# Microcontroller.net
KiCad netlist of a schematic drawn in Altium Designer
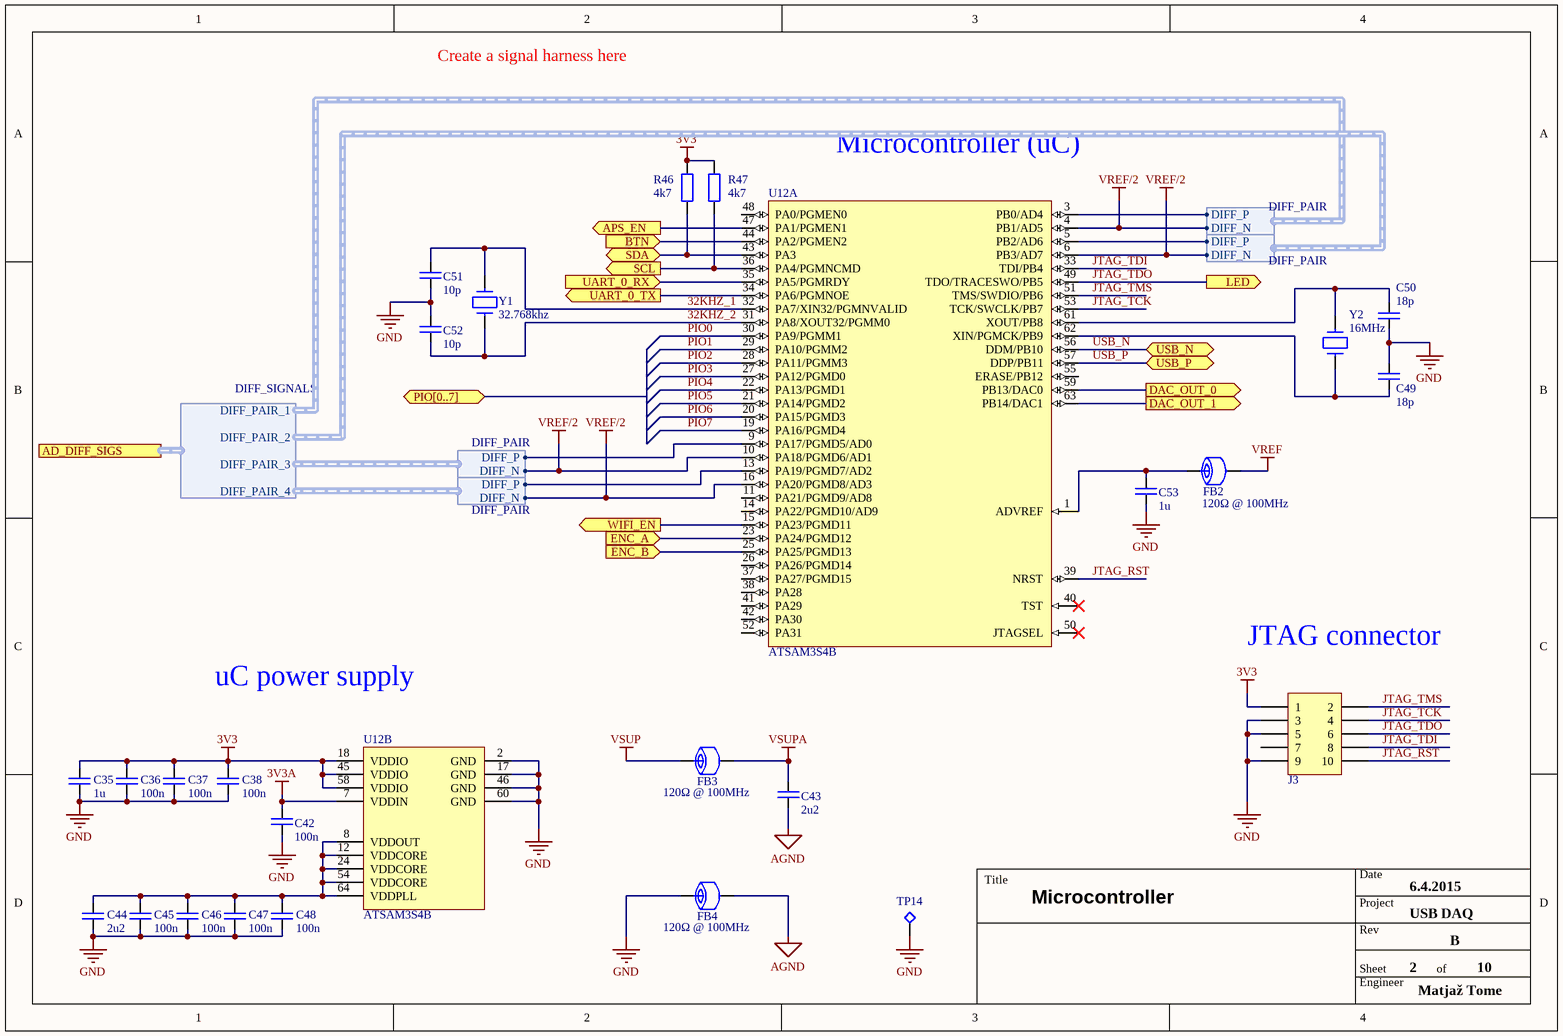
[diagram p0: Microcontroller.SchDoc]

(export (version "E")
  (design (tool "Eeschema 10.0.6"))
  (components
    (comp (ref "C35")
      (value "1u")
      (footprint "C_0603")
      (description "Generic capacitor")
      (libsource (lib "DAQ_REV_B") (part "Capacitor"))
    )
    (comp (ref "C36")
      (value "100n")
      (footprint "C_0603")
      (description "Generic capacitor")
      (libsource (lib "DAQ_REV_B") (part "Capacitor"))
    )
    (comp (ref "C37")
      (value "100n")
      (footprint "C_0603")
      (description "Generic capacitor")
      (libsource (lib "DAQ_REV_B") (part "Capacitor"))
    )
    (comp (ref "C38")
      (value "100n")
      (footprint "C_0603")
      (description "Generic capacitor")
      (libsource (lib "DAQ_REV_B") (part "Capacitor"))
    )
    (comp (ref "C42")
      (value "100n")
      (footprint "C_0603")
      (description "Generic capacitor")
      (libsource (lib "DAQ_REV_B") (part "Capacitor"))
    )
    (comp (ref "C43")
      (value "2u2")
      (footprint "C_0603")
      (description "Generic capacitor")
      (libsource (lib "DAQ_REV_B") (part "Capacitor"))
    )
    (comp (ref "C44")
      (value "2u2")
      (footprint "C_0603")
      (description "Generic capacitor")
      (libsource (lib "DAQ_REV_B") (part "Capacitor"))
    )
    (comp (ref "C45")
      (value "100n")
      (footprint "C_0603")
      (description "Generic capacitor")
      (libsource (lib "DAQ_REV_B") (part "Capacitor"))
    )
    (comp (ref "C46")
      (value "100n")
      (footprint "C_0603")
      (description "Generic capacitor")
      (libsource (lib "DAQ_REV_B") (part "Capacitor"))
    )
    (comp (ref "C47")
      (value "100n")
      (footprint "C_0603")
      (description "Generic capacitor")
      (libsource (lib "DAQ_REV_B") (part "Capacitor"))
    )
    (comp (ref "C48")
      (value "100n")
      (footprint "C_0603")
      (description "Generic capacitor")
      (libsource (lib "DAQ_REV_B") (part "Capacitor"))
    )
    (comp (ref "C49")
      (value "18p")
      (footprint "C_0603")
      (description "Generic capacitor")
      (libsource (lib "DAQ_REV_B") (part "Capacitor"))
    )
    (comp (ref "C50")
      (value "18p")
      (footprint "C_0603")
      (description "Generic capacitor")
      (libsource (lib "DAQ_REV_B") (part "Capacitor"))
    )
    (comp (ref "C51")
      (value "10p")
      (footprint "C_0603")
      (description "Generic capacitor")
      (libsource (lib "DAQ_REV_B") (part "Capacitor"))
    )
    (comp (ref "C52")
      (value "10p")
      (footprint "C_0603")
      (description "Generic capacitor")
      (libsource (lib "DAQ_REV_B") (part "Capacitor"))
    )
    (comp (ref "C53")
      (value "1u")
      (footprint "C_0603")
      (description "Generic capacitor")
      (libsource (lib "DAQ_REV_B") (part "Capacitor"))
    )
    (comp (ref "FB2")
      (value "120Ω @ 100MHz")
      (footprint "SMD_0805")
      (description "Ferrite Bead, 0805 [2012 Metric], 120 ohm, 800 mA, BLM21A Series, 0.15 ohm, ± 25%")
      (fields (field (name "MANUFACTURER") "Murata"))
      (libsource (lib "DAQ_REV_B") (part "BLM21AG121SN1D"))
    )
    (comp (ref "FB3")
      (value "120Ω @ 100MHz")
      (footprint "SMD_0805")
      (description "Ferrite Bead, 0805 [2012 Metric], 120 ohm, 800 mA, BLM21A Series, 0.15 ohm, ± 25%")
      (fields (field (name "MANUFACTURER") "Murata"))
      (libsource (lib "DAQ_REV_B") (part "BLM21AG121SN1D"))
    )
    (comp (ref "FB4")
      (value "120Ω @ 100MHz")
      (footprint "SMD_0805")
      (description "Ferrite Bead, 0805 [2012 Metric], 120 ohm, 800 mA, BLM21A Series, 0.15 ohm, ± 25%")
      (fields (field (name "MANUFACTURER") "Murata"))
      (libsource (lib "DAQ_REV_B") (part "BLM21AG121SN1D"))
    )
    (comp (ref "J3")
      (value "M50-3600542")
      (footprint "HEADER_2X05_1.27mm")
      (description "Pin Header, Board-to-Board, 1.27 mm, 2 Rows, 10 Contacts, Surface Mount, Archer M50 Series")
      (fields (field (name "MANUFACTURER") "Harwin"))
      (libsource (lib "DAQ_REV_B") (part "M50-3600542"))
    )
    (comp (ref "R46")
      (value "4k7")
      (footprint "R_0603")
      (description "Generic resistor")
      (libsource (lib "DAQ_REV_B") (part "Resistor"))
    )
    (comp (ref "R47")
      (value "4k7")
      (footprint "R_0603")
      (description "Generic resistor")
      (libsource (lib "DAQ_REV_B") (part "Resistor"))
    )
    (comp (ref "TP14")
      (value "testpoint")
      (footprint "TP1_FULL")
      (description "testpoint 1.5mm diameter no hole")
      (fields (field (name "PART NUMBER") "XXC0006"))
      (libsource (lib "DAQ_REV_B") (part "Test Point"))
    )
    (comp (ref "U12")
      (value "ATSAM3S4B")
      (footprint "LQFP64")
      (description "Cortex M3 ARM microcontroller")
      (fields (field (name "PART NUMBER") "XAM0003") (field (name "MANUFACTURER") "Atmel"))
      (libsource (lib "DAQ_REV_B") (part "ATSAM3SXB"))
    )
    (comp (ref "Y1")
      (value "32.768khz")
      (footprint "2X6_FLAT")
      (description "Crystal, 32.768 kHz, Cylinder Radial, 6.2mm x 2mm Dia, 12.5 pF, 20 ppm, R26 Series")
      (fields (field (name "PART NUMBER") "XCR0010") (field (name "MANUFACTURER") "RALTRON"))
      (libsource (lib "DAQ_REV_B") (part "R26-32.768- 12.5"))
    )
    (comp (ref "Y2")
      (value "16MHz")
      (footprint "5X3.2")
      (description "Crystal, 16 MHz, SMD, 5mm x 3.2mm, 30 ppm, 18 pF, 30 ppm, 7A Series")
      (fields (field (name "MANUFACTURER") "TCX"))
      (libsource (lib "DAQ_REV_B") (part "7A-16.000MAAJ-T"))
    )
  )
  (nets
    (net (code "3") (name "/32KHZ_1") (class "Default")
      (node (ref "C51") (pin "1") (pinfunction "1_1") (pintype "passive"))
      (node (ref "U12") (pin "32") (pinfunction "PA7/XIN32/PGMNVALID_32") (pintype "bidirectional"))
      (node (ref "Y1") (pin "2") (pinfunction "2_2") (pintype "passive"))
    )
    (net (code "4") (name "/32KHZ_2") (class "Default")
      (node (ref "C52") (pin "1") (pinfunction "1_1") (pintype "passive"))
      (node (ref "U12") (pin "31") (pinfunction "PA8/XOUT32/PGMM0_31") (pintype "bidirectional"))
      (node (ref "Y1") (pin "1") (pinfunction "1_1") (pintype "passive"))
    )
    (net (code "6") (name "/APS_EN") (class "Default")
      (node (ref "U12") (pin "47") (pinfunction "PA1/PGMEN1_47") (pintype "bidirectional"))
    )
    (net (code "7") (name "/BTN") (class "Default")
      (node (ref "U12") (pin "44") (pinfunction "PA2/PGMEN2_44") (pintype "bidirectional"))
    )
    (net (code "8") (name "/DAC_OUT_0") (class "Default")
      (node (ref "U12") (pin "59") (pinfunction "PB13/DAC0_59") (pintype "bidirectional"))
    )
    (net (code "9") (name "/DAC_OUT_1") (class "Default")
      (node (ref "U12") (pin "63") (pinfunction "PB14/DAC1_63") (pintype "bidirectional"))
    )
    (net (code "10") (name "/ENC_A") (class "Default")
      (node (ref "U12") (pin "23") (pinfunction "PA24/PGMD12_23") (pintype "bidirectional"))
    )
    (net (code "11") (name "/ENC_B") (class "Default")
      (node (ref "U12") (pin "25") (pinfunction "PA25/PGMD13_25") (pintype "bidirectional"))
    )
    (net (code "12") (name "/JTAG_RST") (class "Default")
      (node (ref "J3") (pin "10") (pinfunction "10_10") (pintype "passive"))
      (node (ref "U12") (pin "39") (pinfunction "NRST_39") (pintype "bidirectional"))
    )
    (net (code "13") (name "/JTAG_TCK") (class "Default")
      (node (ref "J3") (pin "4") (pinfunction "4_4") (pintype "passive"))
      (node (ref "U12") (pin "53") (pinfunction "TCK/SWCLK/PB7_53") (pintype "bidirectional"))
    )
    (net (code "14") (name "/JTAG_TDI") (class "Default")
      (node (ref "J3") (pin "8") (pinfunction "8_8") (pintype "passive"))
      (node (ref "U12") (pin "33") (pinfunction "TDI/PB4_33") (pintype "bidirectional"))
    )
    (net (code "15") (name "/JTAG_TDO") (class "Default")
      (node (ref "J3") (pin "6") (pinfunction "6_6") (pintype "passive"))
      (node (ref "U12") (pin "49") (pinfunction "TDO/TRACESWO/PB5_49") (pintype "bidirectional"))
    )
    (net (code "16") (name "/JTAG_TMS") (class "Default")
      (node (ref "J3") (pin "2") (pinfunction "2_2") (pintype "passive"))
      (node (ref "U12") (pin "51") (pinfunction "TMS/SWDIO/PB6_51") (pintype "bidirectional"))
    )
    (net (code "17") (name "/PIO0") (class "Default")
      (node (ref "U12") (pin "30") (pinfunction "PA9/PGMM1_30") (pintype "bidirectional"))
    )
    (net (code "18") (name "/PIO1") (class "Default")
      (node (ref "U12") (pin "29") (pinfunction "PA10/PGMM2_29") (pintype "bidirectional"))
    )
    (net (code "19") (name "/PIO2") (class "Default")
      (node (ref "U12") (pin "28") (pinfunction "PA11/PGMM3_28") (pintype "bidirectional"))
    )
    (net (code "20") (name "/PIO3") (class "Default")
      (node (ref "U12") (pin "27") (pinfunction "PA12/PGMD0_27") (pintype "bidirectional"))
    )
    (net (code "21") (name "/PIO4") (class "Default")
      (node (ref "U12") (pin "22") (pinfunction "PA13/PGMD1_22") (pintype "bidirectional"))
    )
    (net (code "22") (name "/PIO5") (class "Default")
      (node (ref "U12") (pin "21") (pinfunction "PA14/PGMD2_21") (pintype "bidirectional"))
    )
    (net (code "23") (name "/PIO6") (class "Default")
      (node (ref "U12") (pin "20") (pinfunction "PA15/PGMD3_20") (pintype "bidirectional"))
    )
    (net (code "24") (name "/PIO7") (class "Default")
      (node (ref "U12") (pin "19") (pinfunction "PA16/PGMD4_19") (pintype "bidirectional"))
    )
    (net (code "26") (name "/SCL") (class "Default")
      (node (ref "R47") (pin "1") (pintype "passive"))
      (node (ref "U12") (pin "36") (pinfunction "PA4/PGMNCMD_36") (pintype "bidirectional"))
    )
    (net (code "27") (name "/SDA") (class "Default")
      (node (ref "R46") (pin "1") (pintype "passive"))
      (node (ref "U12") (pin "43") (pinfunction "PA3_43") (pintype "bidirectional"))
    )
    (net (code "28") (name "/UART_0_RX") (class "Default")
      (node (ref "U12") (pin "35") (pinfunction "PA5/PGMRDY_35") (pintype "bidirectional"))
    )
    (net (code "29") (name "/UART_0_TX") (class "Default")
      (node (ref "U12") (pin "34") (pinfunction "PA6/PGMNOE_34") (pintype "bidirectional"))
    )
    (net (code "30") (name "/USB_N") (class "Default")
      (node (ref "U12") (pin "56") (pinfunction "DDM/PB10_56") (pintype "bidirectional"))
    )
    (net (code "31") (name "/USB_P") (class "Default")
      (node (ref "U12") (pin "57") (pinfunction "DDP/PB11_57") (pintype "bidirectional"))
    )
    (net (code "32") (name "/WIFI_EN") (class "Default")
      (node (ref "U12") (pin "15") (pinfunction "PA23/PGMD11_15") (pintype "bidirectional"))
    )
    (net (code "34") (name "3V3") (class "Default")
      (node (ref "C35") (pin "1") (pinfunction "1_1") (pintype "passive"))
      (node (ref "C36") (pin "1") (pinfunction "1_1") (pintype "passive"))
      (node (ref "C37") (pin "1") (pinfunction "1_1") (pintype "passive"))
      (node (ref "C38") (pin "1") (pinfunction "1_1") (pintype "passive"))
      (node (ref "J3") (pin "1") (pinfunction "1_1") (pintype "passive"))
      (node (ref "R46") (pin "2") (pintype "passive"))
      (node (ref "R47") (pin "2") (pintype "passive"))
      (node (ref "U12") (pin "18") (pinfunction "VDDIO_18") (pintype "power_in"))
      (node (ref "U12") (pin "45") (pinfunction "VDDIO_45") (pintype "power_in"))
      (node (ref "U12") (pin "58") (pinfunction "VDDIO_58") (pintype "power_in"))
    )
    (net (code "35") (name "3V3A") (class "Default")
      (node (ref "C42") (pin "1") (pinfunction "1_1") (pintype "passive"))
      (node (ref "U12") (pin "7") (pinfunction "VDDIN_7") (pintype "power_in"))
    )
    (net (code "36") (name "AGND") (class "Default")
      (node (ref "C43") (pin "2") (pinfunction "2_2") (pintype "passive"))
      (node (ref "FB4") (pin "2") (pintype "passive"))
    )
    (net (code "37") (name "GND") (class "Default")
      (node (ref "C35") (pin "2") (pinfunction "2_2") (pintype "passive"))
      (node (ref "C36") (pin "2") (pinfunction "2_2") (pintype "passive"))
      (node (ref "C37") (pin "2") (pinfunction "2_2") (pintype "passive"))
      (node (ref "C38") (pin "2") (pinfunction "2_2") (pintype "passive"))
      (node (ref "C42") (pin "2") (pinfunction "2_2") (pintype "passive"))
      (node (ref "C44") (pin "2") (pinfunction "2_2") (pintype "passive"))
      (node (ref "C45") (pin "2") (pinfunction "2_2") (pintype "passive"))
      (node (ref "C46") (pin "2") (pinfunction "2_2") (pintype "passive"))
      (node (ref "C47") (pin "2") (pinfunction "2_2") (pintype "passive"))
      (node (ref "C48") (pin "2") (pinfunction "2_2") (pintype "passive"))
      (node (ref "C49") (pin "2") (pinfunction "2_2") (pintype "passive"))
      (node (ref "C50") (pin "2") (pinfunction "2_2") (pintype "passive"))
      (node (ref "C51") (pin "2") (pinfunction "2_2") (pintype "passive"))
      (node (ref "C52") (pin "2") (pinfunction "2_2") (pintype "passive"))
      (node (ref "C53") (pin "2") (pinfunction "2_2") (pintype "passive"))
      (node (ref "FB4") (pin "1") (pintype "passive"))
      (node (ref "J3") (pin "3") (pinfunction "3_3") (pintype "passive"))
      (node (ref "J3") (pin "5") (pinfunction "5_5") (pintype "passive"))
      (node (ref "J3") (pin "9") (pinfunction "9_9") (pintype "passive"))
      (node (ref "TP14") (pin "1") (pinfunction "1_1") (pintype "passive"))
      (node (ref "U12") (pin "17") (pinfunction "GND_17") (pintype "power_in"))
      (node (ref "U12") (pin "2") (pinfunction "GND_2") (pintype "power_in"))
      (node (ref "U12") (pin "46") (pinfunction "GND_46") (pintype "power_in"))
      (node (ref "U12") (pin "60") (pinfunction "GND_60") (pintype "power_in"))
    )
    (net (code "38") (name "Net-(U12A-ADVREF)") (class "Default")
      (node (ref "C53") (pin "1") (pinfunction "1_1") (pintype "passive"))
      (node (ref "FB2") (pin "1") (pintype "passive"))
      (node (ref "U12") (pin "1") (pinfunction "ADVREF_1") (pintype "input"))
    )
    (net (code "39") (name "Net-(U12A-XIN{slash}PGMCK{slash}PB9)") (class "Default")
      (node (ref "C49") (pin "1") (pinfunction "1_1") (pintype "passive"))
      (node (ref "U12") (pin "62") (pinfunction "XIN/PGMCK/PB9_62") (pintype "bidirectional"))
      (node (ref "Y2") (pin "1") (pinfunction "1_1") (pintype "passive"))
    )
    (net (code "40") (name "Net-(U12A-XOUT{slash}PB8)") (class "Default")
      (node (ref "C50") (pin "1") (pinfunction "1_1") (pintype "passive"))
      (node (ref "U12") (pin "61") (pinfunction "XOUT/PB8_61") (pintype "bidirectional"))
      (node (ref "Y2") (pin "2") (pinfunction "2_2") (pintype "passive"))
    )
    (net (code "41") (name "Net-(U12B-VDDOUT)") (class "Default")
      (node (ref "C44") (pin "1") (pinfunction "1_1") (pintype "passive"))
      (node (ref "C45") (pin "1") (pinfunction "1_1") (pintype "passive"))
      (node (ref "C46") (pin "1") (pinfunction "1_1") (pintype "passive"))
      (node (ref "C47") (pin "1") (pinfunction "1_1") (pintype "passive"))
      (node (ref "C48") (pin "1") (pinfunction "1_1") (pintype "passive"))
      (node (ref "U12") (pin "12") (pinfunction "VDDCORE_12") (pintype "power_in"))
      (node (ref "U12") (pin "24") (pinfunction "VDDCORE_24") (pintype "power_in"))
      (node (ref "U12") (pin "54") (pinfunction "VDDCORE_54") (pintype "power_in"))
      (node (ref "U12") (pin "64") (pinfunction "VDDPLL_64") (pintype "power_in"))
      (node (ref "U12") (pin "8") (pinfunction "VDDOUT_8") (pintype "power_in"))
    )
    (net (code "42") (name "VREF") (class "Default") (node (ref "FB2") (pin "2") (pintype "passive")))
    (net (code "43") (name "VREF{slash}2") (class "Default")
      (node (ref "U12") (pin "10") (pinfunction "PA18/PGMD6/AD1_10") (pintype "bidirectional"))
      (node (ref "U12") (pin "16") (pinfunction "PA20/PGMD8/AD3_16") (pintype "bidirectional"))
      (node (ref "U12") (pin "4") (pinfunction "PB1/AD5_4") (pintype "bidirectional"))
      (node (ref "U12") (pin "6") (pinfunction "PB3/AD7_6") (pintype "bidirectional"))
    )
    (net (code "44") (name "VSUP") (class "Default") (node (ref "FB3") (pin "1") (pintype "passive")))
    (net (code "45") (name "VSUPA") (class "Default")
      (node (ref "C43") (pin "1") (pinfunction "1_1") (pintype "passive"))
      (node (ref "FB3") (pin "2") (pintype "passive"))
    )
    (net (code "46") (name "unconnected-(J3-Pad7)") (class "Default")
      (node (ref "J3") (pin "7") (pinfunction "7_7") (pintype "passive"))
    )
    (net (code "47") (name "unconnected-(U12A-ERASE{slash}PB12-Pad55)") (class "Default")
      (node (ref "U12") (pin "55") (pinfunction "ERASE/PB12_55") (pintype "bidirectional"))
    )
    (net (code "48") (name "unconnected-(U12A-JTAGSEL-Pad50)") (class "Default")
      (node (ref "U12") (pin "50") (pinfunction "JTAGSEL_50") (pintype "input+no_connect"))
    )
    (net (code "49") (name "unconnected-(U12A-PA0{slash}PGMEN0-Pad48)") (class "Default")
      (node (ref "U12") (pin "48") (pinfunction "PA0/PGMEN0_48") (pintype "bidirectional"))
    )
    (net (code "50") (name "unconnected-(U12A-PA17{slash}PGMD5{slash}AD0-Pad9)") (class "Default")
      (node (ref "U12") (pin "9") (pinfunction "PA17/PGMD5/AD0_9") (pintype "bidirectional"))
    )
    (net (code "51") (name "unconnected-(U12A-PA19{slash}PGMD7{slash}AD2-Pad13)") (class "Default")
      (node (ref "U12") (pin "13") (pinfunction "PA19/PGMD7/AD2_13") (pintype "bidirectional"))
    )
    (net (code "52") (name "unconnected-(U12A-PA21{slash}PGMD9{slash}AD8-Pad11)") (class "Default")
      (node (ref "U12") (pin "11") (pinfunction "PA21/PGMD9/AD8_11") (pintype "bidirectional"))
    )
    (net (code "53") (name "unconnected-(U12A-PA22{slash}PGMD10{slash}AD9-Pad14)") (class "Default")
      (node (ref "U12") (pin "14") (pinfunction "PA22/PGMD10/AD9_14") (pintype "bidirectional"))
    )
    (net (code "54") (name "unconnected-(U12A-PA26{slash}PGMD14-Pad26)") (class "Default")
      (node (ref "U12") (pin "26") (pinfunction "PA26/PGMD14_26") (pintype "bidirectional"))
    )
    (net (code "55") (name "unconnected-(U12A-PA27{slash}PGMD15-Pad37)") (class "Default")
      (node (ref "U12") (pin "37") (pinfunction "PA27/PGMD15_37") (pintype "bidirectional"))
    )
    (net (code "56") (name "unconnected-(U12A-PA28-Pad38)") (class "Default")
      (node (ref "U12") (pin "38") (pinfunction "PA28_38") (pintype "bidirectional"))
    )
    (net (code "57") (name "unconnected-(U12A-PA29-Pad41)") (class "Default")
      (node (ref "U12") (pin "41") (pinfunction "PA29_41") (pintype "bidirectional"))
    )
    (net (code "58") (name "unconnected-(U12A-PA30-Pad42)") (class "Default")
      (node (ref "U12") (pin "42") (pinfunction "PA30_42") (pintype "bidirectional"))
    )
    (net (code "59") (name "unconnected-(U12A-PA31-Pad52)") (class "Default")
      (node (ref "U12") (pin "52") (pinfunction "PA31_52") (pintype "bidirectional"))
    )
    (net (code "60") (name "unconnected-(U12A-PB0{slash}AD4-Pad3)") (class "Default")
      (node (ref "U12") (pin "3") (pinfunction "PB0/AD4_3") (pintype "bidirectional"))
    )
    (net (code "61") (name "unconnected-(U12A-PB2{slash}AD6-Pad5)") (class "Default")
      (node (ref "U12") (pin "5") (pinfunction "PB2/AD6_5") (pintype "bidirectional"))
    )
    (net (code "62") (name "unconnected-(U12A-TST-Pad40)") (class "Default")
      (node (ref "U12") (pin "40") (pinfunction "TST_40") (pintype "input+no_connect"))
    )
  )
)
